# M133X.net
KiCad netlist of a schematic drawn in EAGLE
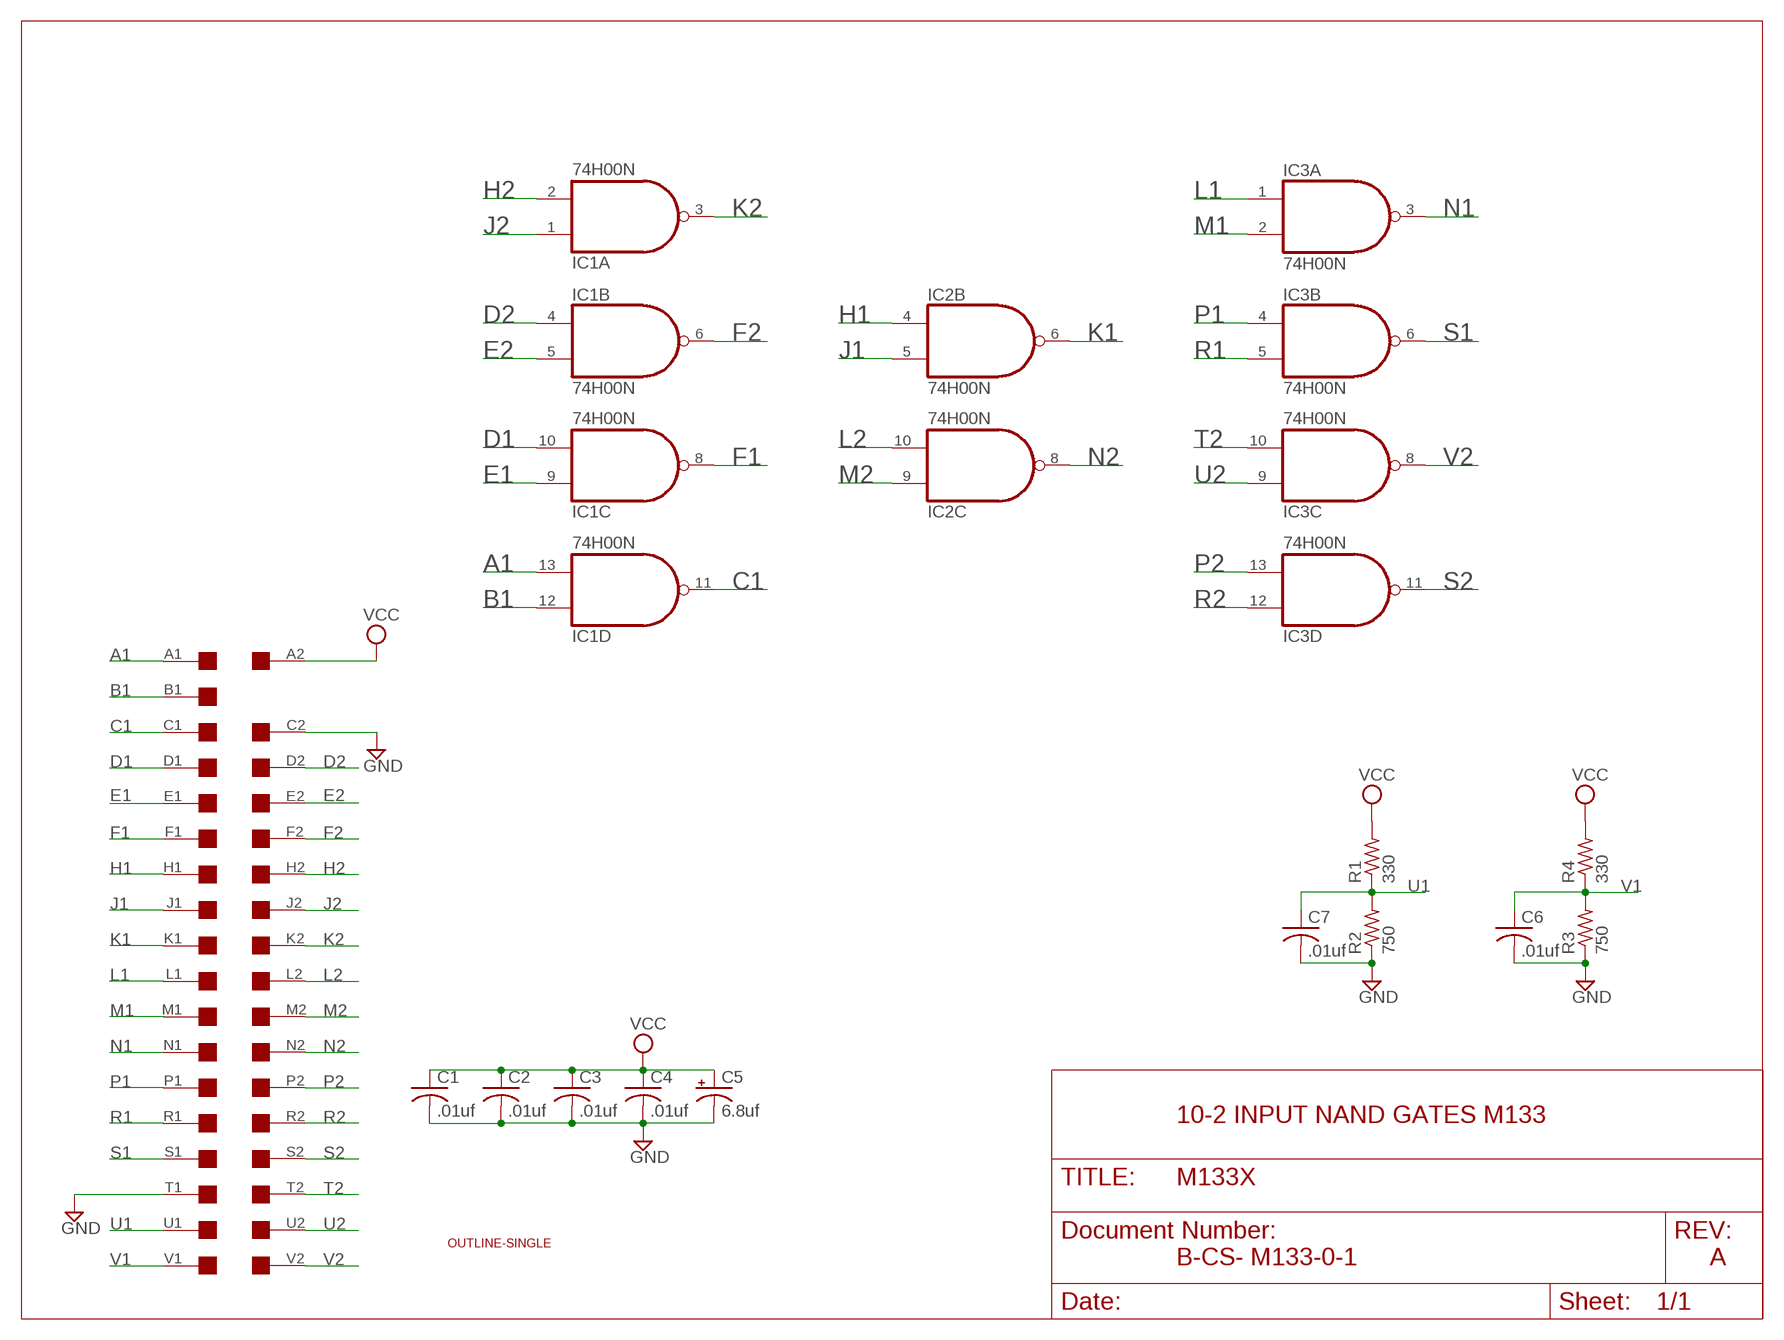
[diagram p0: schematic, sheet 1]

(export (version "E")
  (design (tool "Eeschema 10.0.6"))
  (components
    (comp (ref "C1")
      (value ".01uf")
      (footprint "eagle-import:C050-025X075")
      (libsource (lib "eagle-import") (part "C-US050-025X075"))
    )
    (comp (ref "C2")
      (value ".01uf")
      (footprint "eagle-import:C050-025X075")
      (libsource (lib "eagle-import") (part "C-US050-025X075"))
    )
    (comp (ref "C3")
      (value ".01uf")
      (footprint "eagle-import:C050-025X075")
      (libsource (lib "eagle-import") (part "C-US050-025X075"))
    )
    (comp (ref "C4")
      (value ".01uf")
      (footprint "eagle-import:C050-025X075")
      (libsource (lib "eagle-import") (part "C-US050-025X075"))
    )
    (comp (ref "C5")
      (value "6.8uf")
      (footprint "eagle-import:E15-5")
      (libsource (lib "eagle-import") (part "CPOL-USE15-5AXIAL"))
    )
    (comp (ref "C6")
      (value ".01uf")
      (footprint "eagle-import:C050-025X075")
      (libsource (lib "eagle-import") (part "C-US050-025X075"))
    )
    (comp (ref "C7")
      (value ".01uf")
      (footprint "eagle-import:C050-025X075")
      (libsource (lib "eagle-import") (part "C-US050-025X075"))
    )
    (comp (ref "IC1")
      (value "74H00N")
      (footprint "eagle-import:DIL14")
      (libsource (lib "eagle-import") (part "7400N"))
    )
    (comp (ref "IC2")
      (value "74H00N")
      (footprint "eagle-import:DIL14")
      (libsource (lib "eagle-import") (part "7400N"))
    )
    (comp (ref "IC3")
      (value "74H00N")
      (footprint "eagle-import:DIL14")
      (libsource (lib "eagle-import") (part "7400N"))
    )
    (comp (ref "R1")
      (value "330")
      (footprint "eagle-import:0207_10")
      (libsource (lib "eagle-import") (part "R-US_0207/10"))
    )
    (comp (ref "R2")
      (value "750")
      (footprint "eagle-import:0207_10")
      (libsource (lib "eagle-import") (part "R-US_0207/10"))
    )
    (comp (ref "R3")
      (value "750")
      (footprint "eagle-import:0207_10")
      (libsource (lib "eagle-import") (part "R-US_0207/10"))
    )
    (comp (ref "R4")
      (value "330")
      (footprint "eagle-import:0207_10")
      (libsource (lib "eagle-import") (part "R-US_0207/10"))
    )
    (comp (ref "U$1")
      (value "OUTLINE-SINGLE")
      (footprint "eagle-import:SINGLE")
      (libsource (lib "eagle-import") (part "OUTLINE-SINGLE"))
    )
    (comp (ref "U$4")
      (value "SINGLE")
      (footprint "eagle-import:EDGE-CON2")
      (libsource (lib "eagle-import") (part "SINGLE"))
    )
  )
  (nets
    (net (code "1") (name "/A1") (class "Default")
      (node (ref "IC1") (pin "13") (pinfunction "I1_13") (pintype "input"))
      (node (ref "U$4") (pin "A1") (pinfunction "1_A1") (pintype "bidirectional"))
    )
    (net (code "2") (name "/B1") (class "Default")
      (node (ref "IC1") (pin "12") (pinfunction "I0_12") (pintype "input"))
      (node (ref "U$4") (pin "B1") (pinfunction "1_B1") (pintype "bidirectional"))
    )
    (net (code "3") (name "/C1") (class "Default")
      (node (ref "IC1") (pin "11") (pinfunction "O_11") (pintype "output"))
      (node (ref "U$4") (pin "C1") (pinfunction "1_C1") (pintype "bidirectional"))
    )
    (net (code "4") (name "/D1") (class "Default")
      (node (ref "IC1") (pin "10") (pinfunction "I1_10") (pintype "input"))
      (node (ref "U$4") (pin "D1") (pinfunction "1_D1") (pintype "bidirectional"))
    )
    (net (code "5") (name "/D2") (class "Default")
      (node (ref "IC1") (pin "4") (pinfunction "I0_4") (pintype "input"))
      (node (ref "U$4") (pin "D2") (pinfunction "1_D2") (pintype "bidirectional"))
    )
    (net (code "6") (name "/E1") (class "Default")
      (node (ref "IC1") (pin "9") (pinfunction "I0_9") (pintype "input"))
      (node (ref "U$4") (pin "E1") (pinfunction "1_E1") (pintype "bidirectional"))
    )
    (net (code "7") (name "/E2") (class "Default")
      (node (ref "IC1") (pin "5") (pinfunction "I1_5") (pintype "input"))
      (node (ref "U$4") (pin "E2") (pinfunction "1_E2") (pintype "bidirectional"))
    )
    (net (code "8") (name "/F1") (class "Default")
      (node (ref "IC1") (pin "8") (pinfunction "O_8") (pintype "output"))
      (node (ref "U$4") (pin "F1") (pinfunction "1_F1") (pintype "bidirectional"))
    )
    (net (code "9") (name "/F2") (class "Default")
      (node (ref "IC1") (pin "6") (pinfunction "O_6") (pintype "output"))
      (node (ref "U$4") (pin "F2") (pinfunction "1_F2") (pintype "bidirectional"))
    )
    (net (code "10") (name "/H1") (class "Default")
      (node (ref "IC2") (pin "4") (pinfunction "I0_4") (pintype "input"))
      (node (ref "U$4") (pin "H1") (pinfunction "1_H1") (pintype "bidirectional"))
    )
    (net (code "11") (name "/H2") (class "Default")
      (node (ref "IC1") (pin "2") (pinfunction "I1_2") (pintype "input"))
      (node (ref "U$4") (pin "H2") (pinfunction "1_H2") (pintype "bidirectional"))
    )
    (net (code "12") (name "/J1") (class "Default")
      (node (ref "IC2") (pin "5") (pinfunction "I1_5") (pintype "input"))
      (node (ref "U$4") (pin "J1") (pinfunction "1_J1") (pintype "bidirectional"))
    )
    (net (code "13") (name "/J2") (class "Default")
      (node (ref "IC1") (pin "1") (pinfunction "I0_1") (pintype "input"))
      (node (ref "U$4") (pin "J2") (pinfunction "1_J2") (pintype "bidirectional"))
    )
    (net (code "14") (name "/K1") (class "Default")
      (node (ref "IC2") (pin "6") (pinfunction "O_6") (pintype "output"))
      (node (ref "U$4") (pin "K1") (pinfunction "1_K1") (pintype "bidirectional"))
    )
    (net (code "15") (name "/K2") (class "Default")
      (node (ref "IC1") (pin "3") (pinfunction "O_3") (pintype "output"))
      (node (ref "U$4") (pin "K2") (pinfunction "1_K2") (pintype "bidirectional"))
    )
    (net (code "16") (name "/L1") (class "Default")
      (node (ref "IC3") (pin "1") (pinfunction "I0_1") (pintype "input"))
      (node (ref "U$4") (pin "L1") (pinfunction "1_L1") (pintype "bidirectional"))
    )
    (net (code "17") (name "/L2") (class "Default")
      (node (ref "IC2") (pin "10") (pinfunction "I1_10") (pintype "input"))
      (node (ref "U$4") (pin "L2") (pinfunction "1_L2") (pintype "bidirectional"))
    )
    (net (code "18") (name "/M1") (class "Default")
      (node (ref "IC3") (pin "2") (pinfunction "I1_2") (pintype "input"))
      (node (ref "U$4") (pin "M1") (pinfunction "1_M1") (pintype "bidirectional"))
    )
    (net (code "19") (name "/M2") (class "Default")
      (node (ref "IC2") (pin "9") (pinfunction "I0_9") (pintype "input"))
      (node (ref "U$4") (pin "M2") (pinfunction "1_M2") (pintype "bidirectional"))
    )
    (net (code "20") (name "/N1") (class "Default")
      (node (ref "IC3") (pin "3") (pinfunction "O_3") (pintype "output"))
      (node (ref "U$4") (pin "N1") (pinfunction "1_N1") (pintype "bidirectional"))
    )
    (net (code "21") (name "/N2") (class "Default")
      (node (ref "IC2") (pin "8") (pinfunction "O_8") (pintype "output"))
      (node (ref "U$4") (pin "N2") (pinfunction "1_N2") (pintype "bidirectional"))
    )
    (net (code "22") (name "/P1") (class "Default")
      (node (ref "IC3") (pin "4") (pinfunction "I0_4") (pintype "input"))
      (node (ref "U$4") (pin "P1") (pinfunction "1_P1") (pintype "bidirectional"))
    )
    (net (code "23") (name "/P2") (class "Default")
      (node (ref "IC3") (pin "13") (pinfunction "I1_13") (pintype "input"))
      (node (ref "U$4") (pin "P2") (pinfunction "1_P2") (pintype "bidirectional"))
    )
    (net (code "24") (name "/R1") (class "Default")
      (node (ref "IC3") (pin "5") (pinfunction "I1_5") (pintype "input"))
      (node (ref "U$4") (pin "R1") (pinfunction "1_R1") (pintype "bidirectional"))
    )
    (net (code "25") (name "/R2") (class "Default")
      (node (ref "IC3") (pin "12") (pinfunction "I0_12") (pintype "input"))
      (node (ref "U$4") (pin "R2") (pinfunction "1_R2") (pintype "bidirectional"))
    )
    (net (code "26") (name "/S1") (class "Default")
      (node (ref "IC3") (pin "6") (pinfunction "O_6") (pintype "output"))
      (node (ref "U$4") (pin "S1") (pinfunction "1_S1") (pintype "bidirectional"))
    )
    (net (code "27") (name "/S2") (class "Default")
      (node (ref "IC3") (pin "11") (pinfunction "O_11") (pintype "output"))
      (node (ref "U$4") (pin "S2") (pinfunction "1_S2") (pintype "bidirectional"))
    )
    (net (code "28") (name "/T2") (class "Default")
      (node (ref "IC3") (pin "10") (pinfunction "I1_10") (pintype "input"))
      (node (ref "U$4") (pin "T2") (pinfunction "1_T2") (pintype "bidirectional"))
    )
    (net (code "29") (name "/U1") (class "Default")
      (node (ref "C7") (pin "1") (pinfunction "1_1") (pintype "passive"))
      (node (ref "R1") (pin "1") (pinfunction "1_1") (pintype "passive"))
      (node (ref "R2") (pin "2") (pinfunction "2_2") (pintype "passive"))
      (node (ref "U$4") (pin "U1") (pinfunction "1_U1") (pintype "bidirectional"))
    )
    (net (code "30") (name "/U2") (class "Default")
      (node (ref "IC3") (pin "9") (pinfunction "I0_9") (pintype "input"))
      (node (ref "U$4") (pin "U2") (pinfunction "1_U2") (pintype "bidirectional"))
    )
    (net (code "31") (name "/V1") (class "Default")
      (node (ref "C6") (pin "1") (pinfunction "1_1") (pintype "passive"))
      (node (ref "R3") (pin "2") (pinfunction "2_2") (pintype "passive"))
      (node (ref "R4") (pin "1") (pinfunction "1_1") (pintype "passive"))
      (node (ref "U$4") (pin "V1") (pinfunction "1_V1") (pintype "bidirectional"))
    )
    (net (code "32") (name "/V2") (class "Default")
      (node (ref "IC3") (pin "8") (pinfunction "O_8") (pintype "output"))
      (node (ref "U$4") (pin "V2") (pinfunction "1_V2") (pintype "bidirectional"))
    )
    (net (code "33") (name "GND") (class "Default")
      (node (ref "C1") (pin "2") (pinfunction "2_2") (pintype "passive"))
      (node (ref "C2") (pin "2") (pinfunction "2_2") (pintype "passive"))
      (node (ref "C3") (pin "2") (pinfunction "2_2") (pintype "passive"))
      (node (ref "C4") (pin "2") (pinfunction "2_2") (pintype "passive"))
      (node (ref "C5") (pin "-") (pinfunction "-_-") (pintype "passive"))
      (node (ref "C6") (pin "2") (pinfunction "2_2") (pintype "passive"))
      (node (ref "C7") (pin "2") (pinfunction "2_2") (pintype "passive"))
      (node (ref "R2") (pin "1") (pinfunction "1_1") (pintype "passive"))
      (node (ref "R3") (pin "1") (pinfunction "1_1") (pintype "passive"))
      (node (ref "U$4") (pin "C2") (pinfunction "1_C2") (pintype "bidirectional"))
      (node (ref "U$4") (pin "T1") (pinfunction "1_T1") (pintype "bidirectional"))
    )
    (net (code "34") (name "VCC") (class "Default")
      (node (ref "C1") (pin "1") (pinfunction "1_1") (pintype "passive"))
      (node (ref "C2") (pin "1") (pinfunction "1_1") (pintype "passive"))
      (node (ref "C3") (pin "1") (pinfunction "1_1") (pintype "passive"))
      (node (ref "C4") (pin "1") (pinfunction "1_1") (pintype "passive"))
      (node (ref "C5") (pin "+") (pinfunction "+_+") (pintype "passive"))
      (node (ref "R1") (pin "2") (pinfunction "2_2") (pintype "passive"))
      (node (ref "R4") (pin "2") (pinfunction "2_2") (pintype "passive"))
      (node (ref "U$4") (pin "A2") (pinfunction "1_A2") (pintype "bidirectional"))
    )
  )
)
